# controller_v2.net
KiCad netlist of a schematic drawn in EAGLE
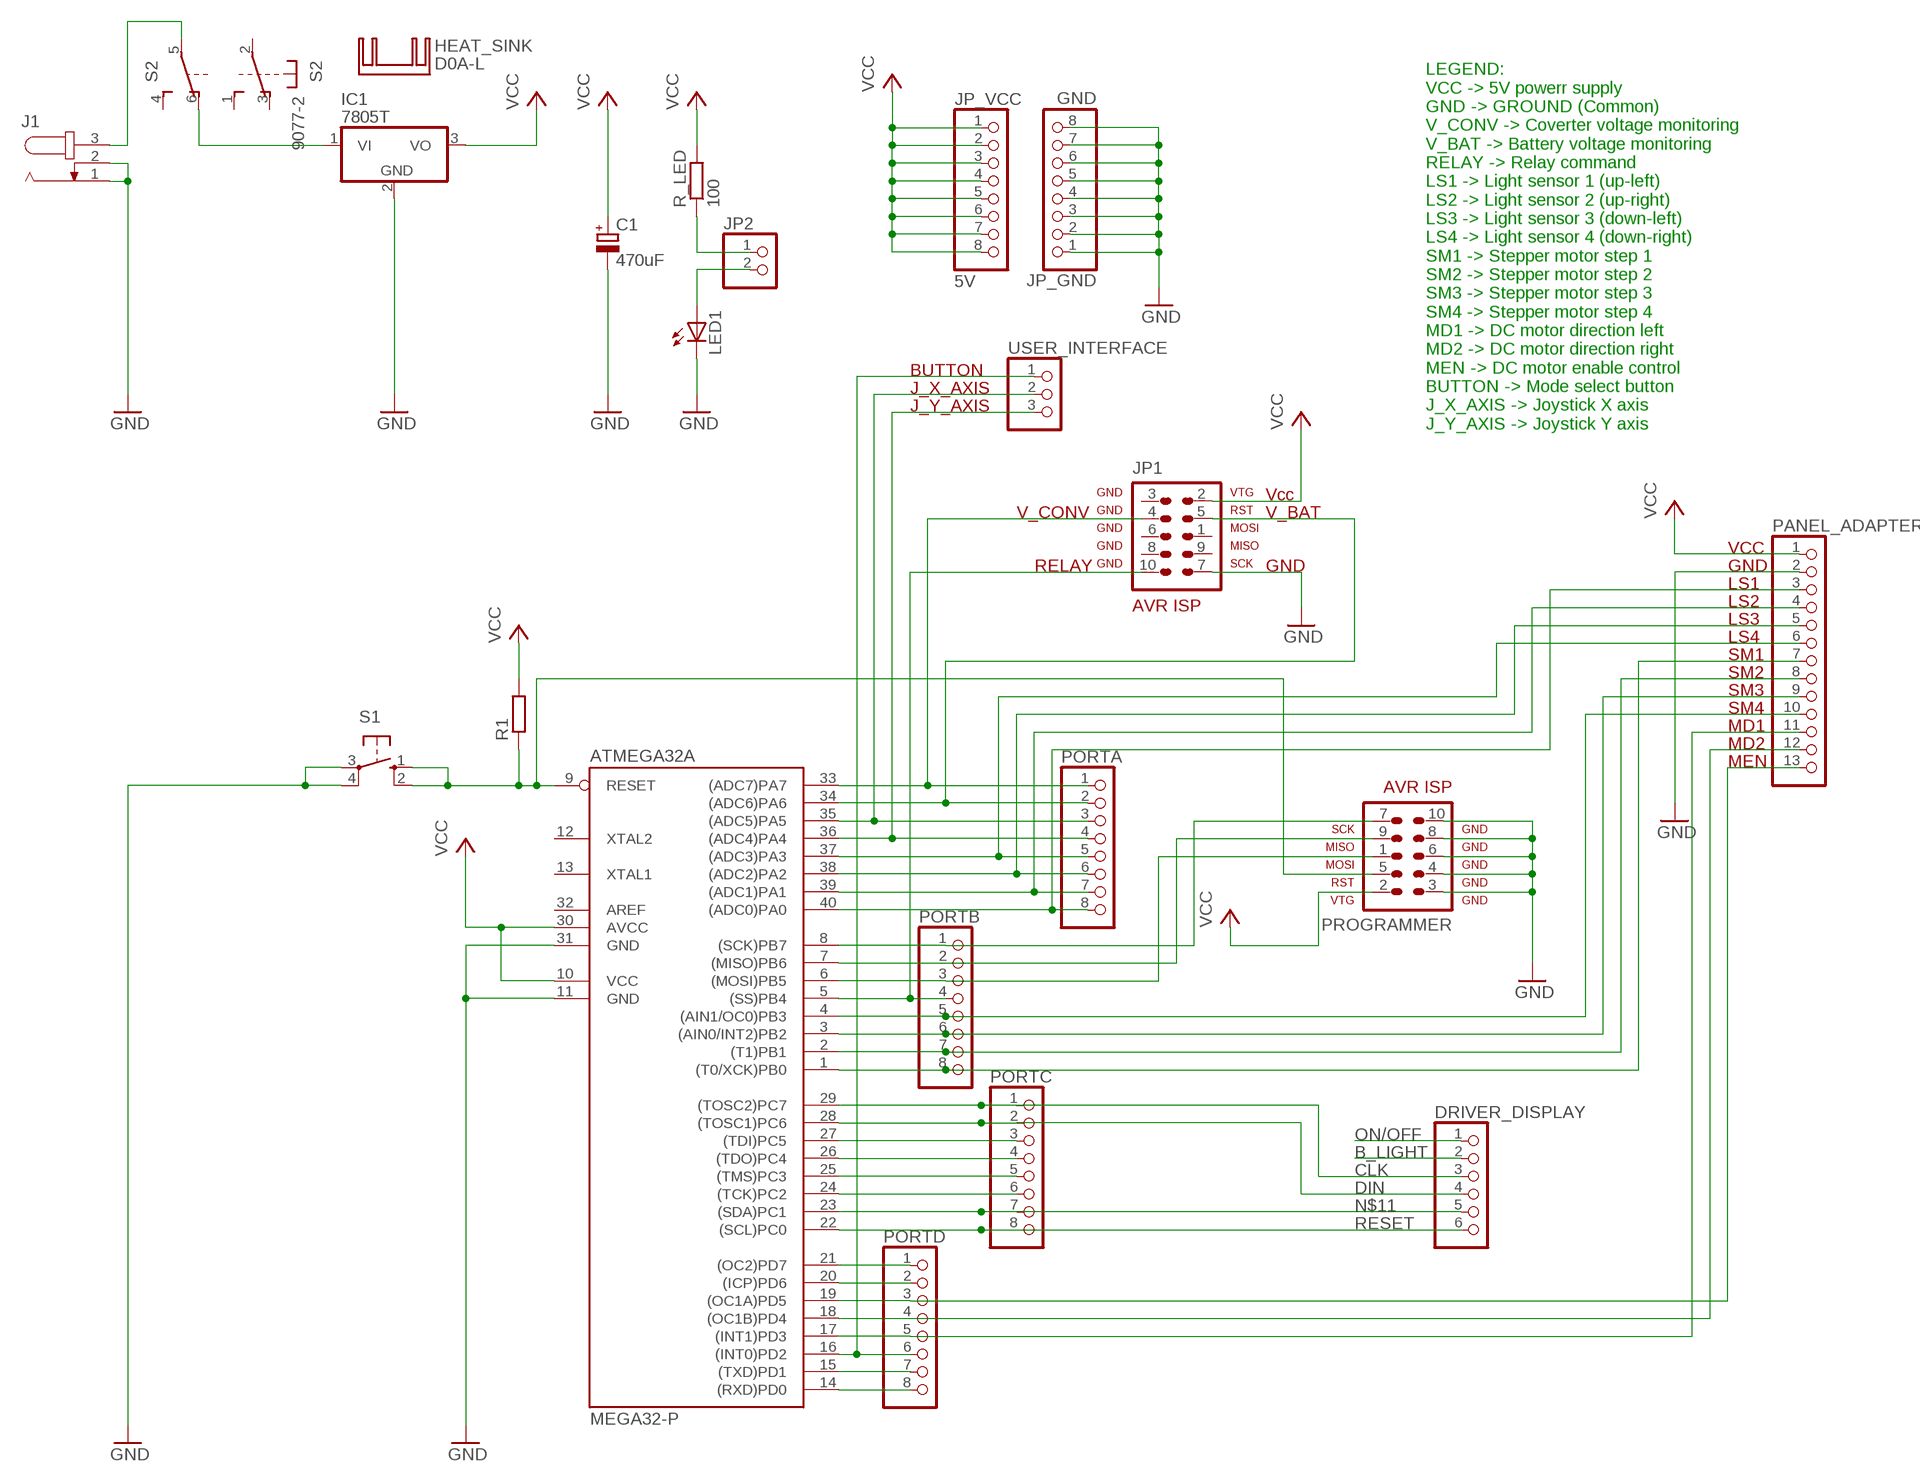
[diagram p0: schematic, sheet 1]

(export (version "E")
  (design (tool "Eeschema 10.0.6"))
  (components
    (comp (ref "ATMEGA32A")
      (value "MEGA32-P")
      (footprint "eagle-import:DIL40")
      (fields (field (name "MPN") "ATMEGA32-16PU"))
      (libsource (lib "eagle-import") (part "MEGA32-P"))
    )
    (comp (ref "C1")
      (value "470uF")
      (footprint "eagle-import:E3,5-8")
      (libsource (lib "eagle-import") (part "CPOL-EUE3.5-8"))
    )
    (comp (ref "DRIVER_DISPLAY")
      (value "PINHD-1X6")
      (footprint "eagle-import:1X06")
      (libsource (lib "eagle-import") (part "PINHD-1X6"))
    )
    (comp (ref "HEAT_SINK")
      (value "D0A-L")
      (footprint "eagle-import:D02A-L")
      (libsource (lib "eagle-import") (part "D0A-L"))
    )
    (comp (ref "IC1")
      (value "7805T")
      (footprint "eagle-import:TO220H")
      (libsource (lib "eagle-import") (part "78T05"))
    )
    (comp (ref "J1")
      (value "JACK-PLUG0")
      (footprint "eagle-import:SPC4077")
      (libsource (lib "eagle-import") (part "JACK-PLUG0"))
    )
    (comp (ref "JP1")
      (value "AVR-ISP-10")
      (footprint "eagle-import:AVR-ISP-10")
      (libsource (lib "eagle-import") (part "AVR-ISP-10"))
    )
    (comp (ref "JP2")
      (value "PINHD-1X2")
      (footprint "eagle-import:1X02")
      (libsource (lib "eagle-import") (part "PINHD-1X2"))
    )
    (comp (ref "JP_GND")
      (value "GND")
      (footprint "eagle-import:1X08")
      (libsource (lib "eagle-import") (part "PINHD-1X8"))
    )
    (comp (ref "JP_VCC")
      (value "5V")
      (footprint "eagle-import:1X08")
      (libsource (lib "eagle-import") (part "PINHD-1X8"))
    )
    (comp (ref "LED1")
      (value "LED5MM")
      (footprint "eagle-import:LED5MM")
      (libsource (lib "eagle-import") (part "LED5MM"))
    )
    (comp (ref "PANEL_ADAPTER")
      (value "PINHD-1X13")
      (footprint "eagle-import:1X13")
      (libsource (lib "eagle-import") (part "PINHD-1X13"))
    )
    (comp (ref "PORTA")
      (value "PINHD-1X8")
      (footprint "eagle-import:1X08")
      (libsource (lib "eagle-import") (part "PINHD-1X8"))
    )
    (comp (ref "PORTB")
      (value "PINHD-1X8")
      (footprint "eagle-import:1X08")
      (libsource (lib "eagle-import") (part "PINHD-1X8"))
    )
    (comp (ref "PORTC")
      (value "PINHD-1X8")
      (footprint "eagle-import:1X08")
      (libsource (lib "eagle-import") (part "PINHD-1X8"))
    )
    (comp (ref "PORTD")
      (value "PINHD-1X8")
      (footprint "eagle-import:1X08")
      (libsource (lib "eagle-import") (part "PINHD-1X8"))
    )
    (comp (ref "PROGRAMMER")
      (value "AVR-ISP-10")
      (footprint "eagle-import:AVR-ISP-10")
      (libsource (lib "eagle-import") (part "AVR-ISP-10"))
    )
    (comp (ref "R1")
      (value "R-EU_0207/10")
      (footprint "eagle-import:0207_10")
      (libsource (lib "eagle-import") (part "R-EU_0207/10"))
    )
    (comp (ref "R_LED")
      (value "100")
      (footprint "eagle-import:0207_10")
      (libsource (lib "eagle-import") (part "R-EU_0207/10"))
    )
    (comp (ref "S1")
      (value "10-XX")
      (footprint "eagle-import:B3F-10XX")
      (fields (field (name "MPN") "B3F-1000"))
      (libsource (lib "eagle-import") (part "10-XX"))
    )
    (comp (ref "S2")
      (value "9077-2")
      (footprint "eagle-import:9077-2")
      (libsource (lib "eagle-import") (part "9077-2"))
    )
    (comp (ref "USER_INTERFACE")
      (value "PINHD-1X3")
      (footprint "eagle-import:1X03")
      (libsource (lib "eagle-import") (part "PINHD-1X3"))
    )
  )
  (nets
    (net (code "1") (name "/B_LIGHT") (class "Default")
      (node (ref "DRIVER_DISPLAY") (pin "2") (pinfunction "2_2") (pintype "passive"))
    )
    (net (code "2") (name "/CLK") (class "Default")
      (node (ref "ATMEGA32A") (pin "29") (pinfunction "(TOSC2)PC7_29") (pintype "bidirectional"))
      (node (ref "DRIVER_DISPLAY") (pin "3") (pinfunction "3_3") (pintype "passive"))
      (node (ref "PORTC") (pin "1") (pinfunction "1_1") (pintype "passive"))
    )
    (net (code "3") (name "/DIN") (class "Default")
      (node (ref "ATMEGA32A") (pin "28") (pinfunction "(TOSC1)PC6_28") (pintype "bidirectional"))
      (node (ref "DRIVER_DISPLAY") (pin "4") (pinfunction "4_4") (pintype "passive"))
      (node (ref "PORTC") (pin "2") (pinfunction "2_2") (pintype "passive"))
    )
    (net (code "4") (name "/N$11") (class "Default")
      (node (ref "ATMEGA32A") (pin "23") (pinfunction "(SDA)PC1_23") (pintype "bidirectional"))
      (node (ref "DRIVER_DISPLAY") (pin "5") (pinfunction "5_5") (pintype "passive"))
      (node (ref "PORTC") (pin "7") (pinfunction "7_7") (pintype "passive"))
    )
    (net (code "5") (name "/ON{slash}OFF") (class "Default")
      (node (ref "DRIVER_DISPLAY") (pin "1") (pinfunction "1_1") (pintype "passive"))
    )
    (net (code "6") (name "/RESET") (class "Default")
      (node (ref "ATMEGA32A") (pin "22") (pinfunction "(SCL)PC0_22") (pintype "bidirectional"))
      (node (ref "DRIVER_DISPLAY") (pin "6") (pinfunction "6_6") (pintype "passive"))
      (node (ref "PORTC") (pin "8") (pinfunction "8_8") (pintype "passive"))
    )
    (net (code "7") (name "GND") (class "Default")
      (node (ref "ATMEGA32A") (pin "11") (pinfunction "GND_11") (pintype "power_in"))
      (node (ref "ATMEGA32A") (pin "31") (pinfunction "GND_31") (pintype "power_in"))
      (node (ref "C1") (pin "-") (pinfunction "-_-") (pintype "passive"))
      (node (ref "IC1") (pin "2") (pinfunction "GND_2") (pintype "passive"))
      (node (ref "J1") (pin "1") (pinfunction "1_1") (pintype "passive"))
      (node (ref "J1") (pin "2") (pinfunction "2_2") (pintype "passive"))
      (node (ref "JP1") (pin "7") (pinfunction "7_7") (pintype "passive"))
      (node (ref "JP_GND") (pin "1") (pinfunction "1_1") (pintype "passive"))
      (node (ref "JP_GND") (pin "2") (pinfunction "2_2") (pintype "passive"))
      (node (ref "JP_GND") (pin "3") (pinfunction "3_3") (pintype "passive"))
      (node (ref "JP_GND") (pin "4") (pinfunction "4_4") (pintype "passive"))
      (node (ref "JP_GND") (pin "5") (pinfunction "5_5") (pintype "passive"))
      (node (ref "JP_GND") (pin "6") (pinfunction "6_6") (pintype "passive"))
      (node (ref "JP_GND") (pin "7") (pinfunction "7_7") (pintype "passive"))
      (node (ref "JP_GND") (pin "8") (pinfunction "8_8") (pintype "passive"))
      (node (ref "LED1") (pin "K") (pinfunction "C_K") (pintype "passive"))
      (node (ref "PANEL_ADAPTER") (pin "2") (pinfunction "2_2") (pintype "passive"))
      (node (ref "PROGRAMMER") (pin "10") (pinfunction "10_10") (pintype "passive"))
      (node (ref "PROGRAMMER") (pin "3") (pinfunction "3_3") (pintype "passive"))
      (node (ref "PROGRAMMER") (pin "4") (pinfunction "4_4") (pintype "passive"))
      (node (ref "PROGRAMMER") (pin "6") (pinfunction "6_6") (pintype "passive"))
      (node (ref "PROGRAMMER") (pin "8") (pinfunction "8_8") (pintype "passive"))
      (node (ref "S1") (pin "3") (pinfunction "P_3") (pintype "passive"))
      (node (ref "S1") (pin "4") (pinfunction "P1_4") (pintype "passive"))
    )
    (net (code "8") (name "Net-(ATMEGA32A-(ADC0)PA0)") (class "Default")
      (node (ref "ATMEGA32A") (pin "40") (pinfunction "(ADC0)PA0_40") (pintype "bidirectional"))
      (node (ref "PANEL_ADAPTER") (pin "3") (pinfunction "3_3") (pintype "passive"))
      (node (ref "PORTA") (pin "8") (pinfunction "8_8") (pintype "passive"))
    )
    (net (code "9") (name "Net-(ATMEGA32A-(ADC1)PA1)") (class "Default")
      (node (ref "ATMEGA32A") (pin "39") (pinfunction "(ADC1)PA1_39") (pintype "bidirectional"))
      (node (ref "PANEL_ADAPTER") (pin "4") (pinfunction "4_4") (pintype "passive"))
      (node (ref "PORTA") (pin "7") (pinfunction "7_7") (pintype "passive"))
    )
    (net (code "10") (name "Net-(ATMEGA32A-(ADC2)PA2)") (class "Default")
      (node (ref "ATMEGA32A") (pin "38") (pinfunction "(ADC2)PA2_38") (pintype "bidirectional"))
      (node (ref "PANEL_ADAPTER") (pin "5") (pinfunction "5_5") (pintype "passive"))
      (node (ref "PORTA") (pin "6") (pinfunction "6_6") (pintype "passive"))
    )
    (net (code "11") (name "Net-(ATMEGA32A-(ADC3)PA3)") (class "Default")
      (node (ref "ATMEGA32A") (pin "37") (pinfunction "(ADC3)PA3_37") (pintype "bidirectional"))
      (node (ref "PANEL_ADAPTER") (pin "6") (pinfunction "6_6") (pintype "passive"))
      (node (ref "PORTA") (pin "5") (pinfunction "5_5") (pintype "passive"))
    )
    (net (code "12") (name "Net-(ATMEGA32A-(ADC4)PA4)") (class "Default")
      (node (ref "ATMEGA32A") (pin "36") (pinfunction "(ADC4)PA4_36") (pintype "bidirectional"))
      (node (ref "PORTA") (pin "4") (pinfunction "4_4") (pintype "passive"))
      (node (ref "USER_INTERFACE") (pin "3") (pinfunction "3_3") (pintype "passive"))
    )
    (net (code "13") (name "Net-(ATMEGA32A-(ADC5)PA5)") (class "Default")
      (node (ref "ATMEGA32A") (pin "35") (pinfunction "(ADC5)PA5_35") (pintype "bidirectional"))
      (node (ref "PORTA") (pin "3") (pinfunction "3_3") (pintype "passive"))
      (node (ref "USER_INTERFACE") (pin "2") (pinfunction "2_2") (pintype "passive"))
    )
    (net (code "14") (name "Net-(ATMEGA32A-(ADC6)PA6)") (class "Default")
      (node (ref "ATMEGA32A") (pin "34") (pinfunction "(ADC6)PA6_34") (pintype "bidirectional"))
      (node (ref "JP1") (pin "5") (pinfunction "5_5") (pintype "passive"))
      (node (ref "PORTA") (pin "2") (pinfunction "2_2") (pintype "passive"))
    )
    (net (code "15") (name "Net-(ATMEGA32A-(ADC7)PA7)") (class "Default")
      (node (ref "ATMEGA32A") (pin "33") (pinfunction "(ADC7)PA7_33") (pintype "bidirectional"))
      (node (ref "JP1") (pin "4") (pinfunction "4_4") (pintype "passive"))
      (node (ref "PORTA") (pin "1") (pinfunction "1_1") (pintype "passive"))
    )
    (net (code "16") (name "Net-(ATMEGA32A-(AIN0{slash}INT2)PB2)") (class "Default")
      (node (ref "ATMEGA32A") (pin "3") (pinfunction "(AIN0/INT2)PB2_3") (pintype "bidirectional"))
      (node (ref "PANEL_ADAPTER") (pin "9") (pinfunction "9_9") (pintype "passive"))
      (node (ref "PORTB") (pin "6") (pinfunction "6_6") (pintype "passive"))
    )
    (net (code "17") (name "Net-(ATMEGA32A-(AIN1{slash}OC0)PB3)") (class "Default")
      (node (ref "ATMEGA32A") (pin "4") (pinfunction "(AIN1/OC0)PB3_4") (pintype "bidirectional"))
      (node (ref "PANEL_ADAPTER") (pin "10") (pinfunction "10_10") (pintype "passive"))
      (node (ref "PORTB") (pin "5") (pinfunction "5_5") (pintype "passive"))
    )
    (net (code "18") (name "Net-(ATMEGA32A-(ICP)PD6)") (class "Default")
      (node (ref "ATMEGA32A") (pin "20") (pinfunction "(ICP)PD6_20") (pintype "bidirectional"))
      (node (ref "PORTD") (pin "2") (pinfunction "2_2") (pintype "passive"))
    )
    (net (code "19") (name "Net-(ATMEGA32A-(INT0)PD2)") (class "Default")
      (node (ref "ATMEGA32A") (pin "16") (pinfunction "(INT0)PD2_16") (pintype "bidirectional"))
      (node (ref "PORTD") (pin "6") (pinfunction "6_6") (pintype "passive"))
      (node (ref "USER_INTERFACE") (pin "1") (pinfunction "1_1") (pintype "passive"))
    )
    (net (code "20") (name "Net-(ATMEGA32A-(INT1)PD3)") (class "Default")
      (node (ref "ATMEGA32A") (pin "17") (pinfunction "(INT1)PD3_17") (pintype "bidirectional"))
      (node (ref "PANEL_ADAPTER") (pin "11") (pinfunction "11_11") (pintype "passive"))
      (node (ref "PORTD") (pin "5") (pinfunction "5_5") (pintype "passive"))
    )
    (net (code "21") (name "Net-(ATMEGA32A-(MISO)PB6)") (class "Default")
      (node (ref "ATMEGA32A") (pin "7") (pinfunction "(MISO)PB6_7") (pintype "bidirectional"))
      (node (ref "PORTB") (pin "2") (pinfunction "2_2") (pintype "passive"))
      (node (ref "PROGRAMMER") (pin "9") (pinfunction "9_9") (pintype "passive"))
    )
    (net (code "22") (name "Net-(ATMEGA32A-(MOSI)PB5)") (class "Default")
      (node (ref "ATMEGA32A") (pin "6") (pinfunction "(MOSI)PB5_6") (pintype "bidirectional"))
      (node (ref "PORTB") (pin "3") (pinfunction "3_3") (pintype "passive"))
      (node (ref "PROGRAMMER") (pin "1") (pinfunction "1_1") (pintype "passive"))
    )
    (net (code "23") (name "Net-(ATMEGA32A-(OC1A)PD5)") (class "Default")
      (node (ref "ATMEGA32A") (pin "19") (pinfunction "(OC1A)PD5_19") (pintype "bidirectional"))
      (node (ref "PANEL_ADAPTER") (pin "13") (pinfunction "13_13") (pintype "passive"))
      (node (ref "PORTD") (pin "3") (pinfunction "3_3") (pintype "passive"))
    )
    (net (code "24") (name "Net-(ATMEGA32A-(OC1B)PD4)") (class "Default")
      (node (ref "ATMEGA32A") (pin "18") (pinfunction "(OC1B)PD4_18") (pintype "bidirectional"))
      (node (ref "PANEL_ADAPTER") (pin "12") (pinfunction "12_12") (pintype "passive"))
      (node (ref "PORTD") (pin "4") (pinfunction "4_4") (pintype "passive"))
    )
    (net (code "25") (name "Net-(ATMEGA32A-(OC2)PD7)") (class "Default")
      (node (ref "ATMEGA32A") (pin "21") (pinfunction "(OC2)PD7_21") (pintype "bidirectional"))
      (node (ref "PORTD") (pin "1") (pinfunction "1_1") (pintype "passive"))
    )
    (net (code "26") (name "Net-(ATMEGA32A-(RXD)PD0)") (class "Default")
      (node (ref "ATMEGA32A") (pin "14") (pinfunction "(RXD)PD0_14") (pintype "bidirectional"))
      (node (ref "PORTD") (pin "8") (pinfunction "8_8") (pintype "passive"))
    )
    (net (code "27") (name "Net-(ATMEGA32A-(SCK)PB7)") (class "Default")
      (node (ref "ATMEGA32A") (pin "8") (pinfunction "(SCK)PB7_8") (pintype "bidirectional"))
      (node (ref "PORTB") (pin "1") (pinfunction "1_1") (pintype "passive"))
      (node (ref "PROGRAMMER") (pin "7") (pinfunction "7_7") (pintype "passive"))
    )
    (net (code "28") (name "Net-(ATMEGA32A-(SS)PB4)") (class "Default")
      (node (ref "ATMEGA32A") (pin "5") (pinfunction "(SS)PB4_5") (pintype "bidirectional"))
      (node (ref "JP1") (pin "10") (pinfunction "10_10") (pintype "passive"))
      (node (ref "PORTB") (pin "4") (pinfunction "4_4") (pintype "passive"))
    )
    (net (code "29") (name "Net-(ATMEGA32A-(T0{slash}XCK)PB0)") (class "Default")
      (node (ref "ATMEGA32A") (pin "1") (pinfunction "(T0/XCK)PB0_1") (pintype "bidirectional"))
      (node (ref "PANEL_ADAPTER") (pin "7") (pinfunction "7_7") (pintype "passive"))
      (node (ref "PORTB") (pin "8") (pinfunction "8_8") (pintype "passive"))
    )
    (net (code "30") (name "Net-(ATMEGA32A-(T1)PB1)") (class "Default")
      (node (ref "ATMEGA32A") (pin "2") (pinfunction "(T1)PB1_2") (pintype "bidirectional"))
      (node (ref "PANEL_ADAPTER") (pin "8") (pinfunction "8_8") (pintype "passive"))
      (node (ref "PORTB") (pin "7") (pinfunction "7_7") (pintype "passive"))
    )
    (net (code "31") (name "Net-(ATMEGA32A-(TCK)PC2)") (class "Default")
      (node (ref "ATMEGA32A") (pin "24") (pinfunction "(TCK)PC2_24") (pintype "bidirectional"))
      (node (ref "PORTC") (pin "6") (pinfunction "6_6") (pintype "passive"))
    )
    (net (code "32") (name "Net-(ATMEGA32A-(TDI)PC5)") (class "Default")
      (node (ref "ATMEGA32A") (pin "27") (pinfunction "(TDI)PC5_27") (pintype "bidirectional"))
      (node (ref "PORTC") (pin "3") (pinfunction "3_3") (pintype "passive"))
    )
    (net (code "33") (name "Net-(ATMEGA32A-(TDO)PC4)") (class "Default")
      (node (ref "ATMEGA32A") (pin "26") (pinfunction "(TDO)PC4_26") (pintype "bidirectional"))
      (node (ref "PORTC") (pin "4") (pinfunction "4_4") (pintype "passive"))
    )
    (net (code "34") (name "Net-(ATMEGA32A-(TMS)PC3)") (class "Default")
      (node (ref "ATMEGA32A") (pin "25") (pinfunction "(TMS)PC3_25") (pintype "bidirectional"))
      (node (ref "PORTC") (pin "5") (pinfunction "5_5") (pintype "passive"))
    )
    (net (code "35") (name "Net-(ATMEGA32A-(TXD)PD1)") (class "Default")
      (node (ref "ATMEGA32A") (pin "15") (pinfunction "(TXD)PD1_15") (pintype "bidirectional"))
      (node (ref "PORTD") (pin "7") (pinfunction "7_7") (pintype "passive"))
    )
    (net (code "36") (name "Net-(ATMEGA32A-RESET)") (class "Default")
      (node (ref "ATMEGA32A") (pin "9") (pinfunction "RESET_9") (pintype "input"))
      (node (ref "PROGRAMMER") (pin "5") (pinfunction "5_5") (pintype "passive"))
      (node (ref "R1") (pin "1") (pinfunction "1_1") (pintype "passive"))
      (node (ref "S1") (pin "1") (pinfunction "S_1") (pintype "passive"))
      (node (ref "S1") (pin "2") (pinfunction "S1_2") (pintype "passive"))
    )
    (net (code "37") (name "Net-(IC1-VI)") (class "Default")
      (node (ref "IC1") (pin "1") (pinfunction "VI_1") (pintype "input"))
      (node (ref "S2") (pin "6") (pinfunction "O_6") (pintype "passive"))
    )
    (net (code "38") (name "Net-(JP2-Pad1)") (class "Default")
      (node (ref "JP2") (pin "1") (pinfunction "1_1") (pintype "passive"))
      (node (ref "R_LED") (pin "1") (pinfunction "1_1") (pintype "passive"))
    )
    (net (code "39") (name "Net-(JP2-Pad2)") (class "Default")
      (node (ref "JP2") (pin "2") (pinfunction "2_2") (pintype "passive"))
      (node (ref "LED1") (pin "A") (pinfunction "A_A") (pintype "passive"))
    )
    (net (code "40") (name "Net-(S2B-P)") (class "Default")
      (node (ref "J1") (pin "3") (pinfunction "3_3") (pintype "passive"))
      (node (ref "S2") (pin "5") (pinfunction "P_5") (pintype "passive"))
    )
    (net (code "41") (name "VCC") (class "Default")
      (node (ref "ATMEGA32A") (pin "10") (pinfunction "VCC_10") (pintype "power_in"))
      (node (ref "ATMEGA32A") (pin "30") (pinfunction "AVCC_30") (pintype "power_in"))
      (node (ref "C1") (pin "+") (pinfunction "+_+") (pintype "passive"))
      (node (ref "IC1") (pin "3") (pinfunction "VO_3") (pintype "passive"))
      (node (ref "JP1") (pin "2") (pinfunction "2_2") (pintype "passive"))
      (node (ref "JP_VCC") (pin "1") (pinfunction "1_1") (pintype "passive"))
      (node (ref "JP_VCC") (pin "2") (pinfunction "2_2") (pintype "passive"))
      (node (ref "JP_VCC") (pin "3") (pinfunction "3_3") (pintype "passive"))
      (node (ref "JP_VCC") (pin "4") (pinfunction "4_4") (pintype "passive"))
      (node (ref "JP_VCC") (pin "5") (pinfunction "5_5") (pintype "passive"))
      (node (ref "JP_VCC") (pin "6") (pinfunction "6_6") (pintype "passive"))
      (node (ref "JP_VCC") (pin "7") (pinfunction "7_7") (pintype "passive"))
      (node (ref "JP_VCC") (pin "8") (pinfunction "8_8") (pintype "passive"))
      (node (ref "PANEL_ADAPTER") (pin "1") (pinfunction "1_1") (pintype "passive"))
      (node (ref "PROGRAMMER") (pin "2") (pinfunction "2_2") (pintype "passive"))
      (node (ref "R1") (pin "2") (pinfunction "2_2") (pintype "passive"))
      (node (ref "R_LED") (pin "2") (pinfunction "2_2") (pintype "passive"))
    )
    (net (code "42") (name "unconnected-(ATMEGA32A-AREF-Pad32)") (class "Default")
      (node (ref "ATMEGA32A") (pin "32") (pinfunction "AREF_32") (pintype "passive"))
    )
    (net (code "43") (name "unconnected-(ATMEGA32A-XTAL1-Pad13)") (class "Default")
      (node (ref "ATMEGA32A") (pin "13") (pinfunction "XTAL1_13") (pintype "bidirectional"))
    )
    (net (code "44") (name "unconnected-(ATMEGA32A-XTAL2-Pad12)") (class "Default")
      (node (ref "ATMEGA32A") (pin "12") (pinfunction "XTAL2_12") (pintype "bidirectional"))
    )
    (net (code "45") (name "unconnected-(JP1-Pad1)") (class "Default")
      (node (ref "JP1") (pin "1") (pinfunction "1_1") (pintype "passive"))
    )
    (net (code "46") (name "unconnected-(JP1-Pad3)") (class "Default")
      (node (ref "JP1") (pin "3") (pinfunction "3_3") (pintype "passive"))
    )
    (net (code "47") (name "unconnected-(JP1-Pad6)") (class "Default")
      (node (ref "JP1") (pin "6") (pinfunction "6_6") (pintype "passive"))
    )
    (net (code "48") (name "unconnected-(JP1-Pad8)") (class "Default")
      (node (ref "JP1") (pin "8") (pinfunction "8_8") (pintype "passive"))
    )
    (net (code "49") (name "unconnected-(JP1-Pad9)") (class "Default")
      (node (ref "JP1") (pin "9") (pinfunction "9_9") (pintype "passive"))
    )
    (net (code "50") (name "unconnected-(S2A-O-Pad3)") (class "Default")
      (node (ref "S2") (pin "3") (pinfunction "O_3") (pintype "passive"))
    )
    (net (code "51") (name "unconnected-(S2A-P-Pad2)") (class "Default")
      (node (ref "S2") (pin "2") (pinfunction "P_2") (pintype "passive"))
    )
    (net (code "52") (name "unconnected-(S2A-S-Pad1)") (class "Default")
      (node (ref "S2") (pin "1") (pinfunction "S_1") (pintype "passive"))
    )
    (net (code "53") (name "unconnected-(S2B-S-Pad4)") (class "Default")
      (node (ref "S2") (pin "4") (pinfunction "S_4") (pintype "passive"))
    )
  )
)
